# eu-gate.net
KiCad netlist of a schematic drawn in EAGLE
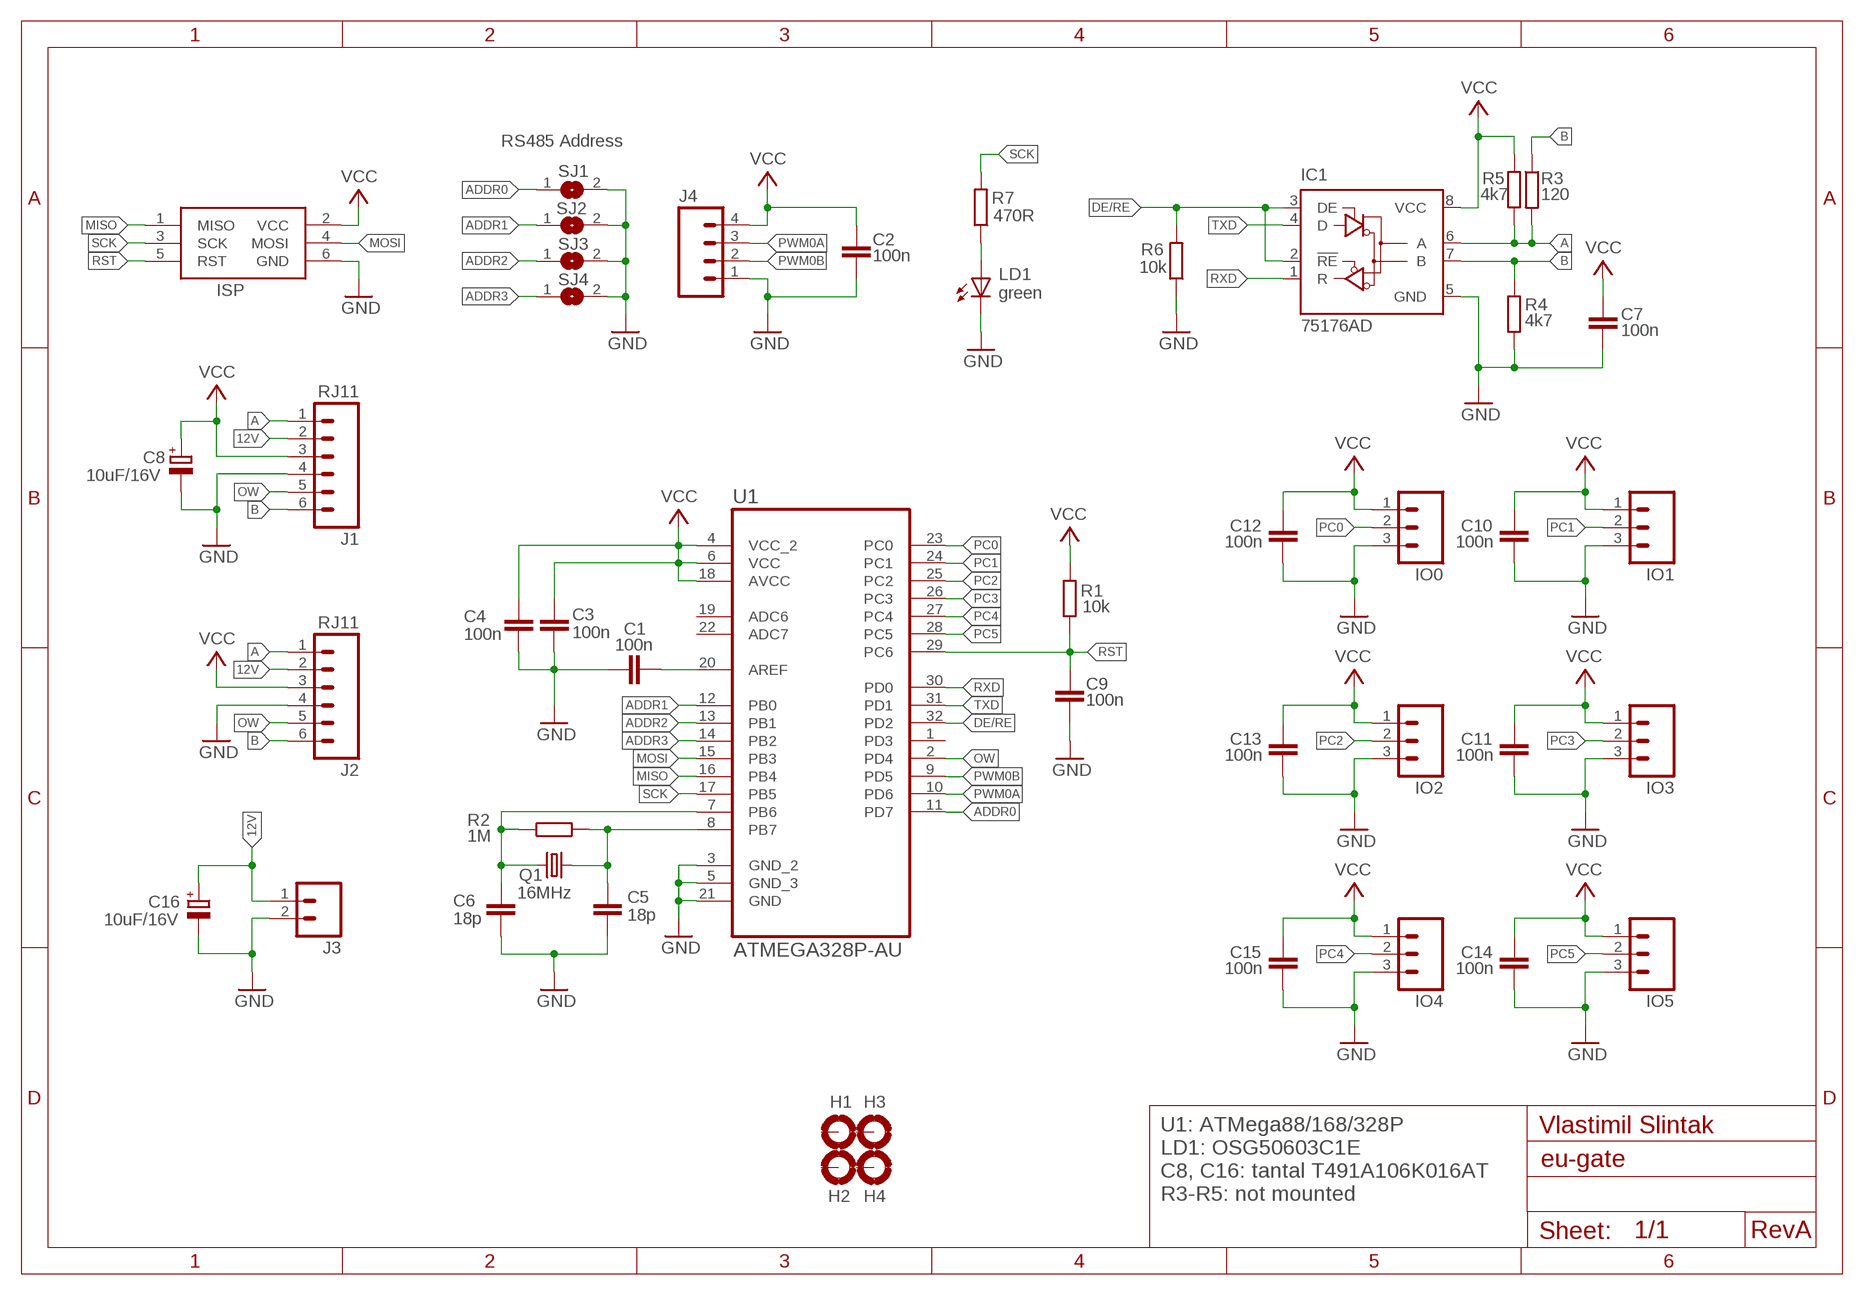
[diagram p0: schematic, sheet 1]

(export (version "E")
  (design (tool "Eeschema 10.0.6"))
  (components
    (comp (ref "C1")
      (value "100n")
      (footprint "eagle-import:C0603")
      (libsource (lib "eagle-import") (part "C-EUC0603"))
    )
    (comp (ref "C2")
      (value "100n")
      (footprint "eagle-import:C0603")
      (libsource (lib "eagle-import") (part "C-EUC0603"))
    )
    (comp (ref "C3")
      (value "100n")
      (footprint "eagle-import:C0603")
      (libsource (lib "eagle-import") (part "C-EUC0603"))
    )
    (comp (ref "C4")
      (value "100n")
      (footprint "eagle-import:C0603")
      (libsource (lib "eagle-import") (part "C-EUC0603"))
    )
    (comp (ref "C5")
      (value "18p")
      (footprint "eagle-import:C0603")
      (libsource (lib "eagle-import") (part "C-EUC0603"))
    )
    (comp (ref "C6")
      (value "18p")
      (footprint "eagle-import:C0603")
      (libsource (lib "eagle-import") (part "C-EUC0603"))
    )
    (comp (ref "C7")
      (value "100n")
      (footprint "eagle-import:C0603")
      (libsource (lib "eagle-import") (part "C-EUC0603"))
    )
    (comp (ref "C8")
      (value "10uF/16V")
      (footprint "eagle-import:SMC_A")
      (libsource (lib "eagle-import") (part "CPOL-EUSMCA"))
    )
    (comp (ref "C9")
      (value "100n")
      (footprint "eagle-import:C0603")
      (libsource (lib "eagle-import") (part "C-EUC0603"))
    )
    (comp (ref "C10")
      (value "100n")
      (footprint "eagle-import:C0603")
      (libsource (lib "eagle-import") (part "C-EUC0603"))
    )
    (comp (ref "C11")
      (value "100n")
      (footprint "eagle-import:C0603")
      (libsource (lib "eagle-import") (part "C-EUC0603"))
    )
    (comp (ref "C12")
      (value "100n")
      (footprint "eagle-import:C0603")
      (libsource (lib "eagle-import") (part "C-EUC0603"))
    )
    (comp (ref "C13")
      (value "100n")
      (footprint "eagle-import:C0603")
      (libsource (lib "eagle-import") (part "C-EUC0603"))
    )
    (comp (ref "C14")
      (value "100n")
      (footprint "eagle-import:C0603")
      (libsource (lib "eagle-import") (part "C-EUC0603"))
    )
    (comp (ref "C15")
      (value "100n")
      (footprint "eagle-import:C0603")
      (libsource (lib "eagle-import") (part "C-EUC0603"))
    )
    (comp (ref "C16")
      (value "10uF/16V")
      (footprint "eagle-import:SMC_A")
      (libsource (lib "eagle-import") (part "CPOL-EUSMCA"))
    )
    (comp (ref "H1")
      (value "MOUNT-PAD-ROUND3.0")
      (footprint "eagle-import:3,0-PAD")
      (libsource (lib "eagle-import") (part "MOUNT-PAD-ROUND3.0"))
    )
    (comp (ref "H2")
      (value "MOUNT-PAD-ROUND3.0")
      (footprint "eagle-import:3,0-PAD")
      (libsource (lib "eagle-import") (part "MOUNT-PAD-ROUND3.0"))
    )
    (comp (ref "H3")
      (value "MOUNT-PAD-ROUND3.0")
      (footprint "eagle-import:3,0-PAD")
      (libsource (lib "eagle-import") (part "MOUNT-PAD-ROUND3.0"))
    )
    (comp (ref "H4")
      (value "MOUNT-PAD-ROUND3.0")
      (footprint "eagle-import:3,0-PAD")
      (libsource (lib "eagle-import") (part "MOUNT-PAD-ROUND3.0"))
    )
    (comp (ref "IC1")
      (value "75176AD")
      (footprint "eagle-import:D_R-PDSO-G8")
      (libsource (lib "eagle-import") (part "75176AD"))
    )
    (comp (ref "IO0")
      (value "M03POLAR")
      (footprint "eagle-import:MOLEX-1X3")
      (libsource (lib "eagle-import") (part "M03POLAR"))
    )
    (comp (ref "IO1")
      (value "M03POLAR")
      (footprint "eagle-import:MOLEX-1X3")
      (libsource (lib "eagle-import") (part "M03POLAR"))
    )
    (comp (ref "IO2")
      (value "M03POLAR")
      (footprint "eagle-import:MOLEX-1X3")
      (libsource (lib "eagle-import") (part "M03POLAR"))
    )
    (comp (ref "IO3")
      (value "M03POLAR")
      (footprint "eagle-import:MOLEX-1X3")
      (libsource (lib "eagle-import") (part "M03POLAR"))
    )
    (comp (ref "IO4")
      (value "M03POLAR")
      (footprint "eagle-import:MOLEX-1X3")
      (libsource (lib "eagle-import") (part "M03POLAR"))
    )
    (comp (ref "IO5")
      (value "M03POLAR")
      (footprint "eagle-import:MOLEX-1X3")
      (libsource (lib "eagle-import") (part "M03POLAR"))
    )
    (comp (ref "ISP")
      (value "AVRISP-6")
      (footprint "eagle-import:AVRISP")
      (libsource (lib "eagle-import") (part "AVRISP-6"))
    )
    (comp (ref "J1")
      (value "RJ11")
      (footprint "eagle-import:RJ11-6")
      (libsource (lib "eagle-import") (part "RJ11-6PTH"))
    )
    (comp (ref "J2")
      (value "RJ11")
      (footprint "eagle-import:RJ11-6")
      (libsource (lib "eagle-import") (part "RJ11-6PTH"))
    )
    (comp (ref "J3")
      (value "M02POLAR")
      (footprint "eagle-import:MOLEX-1X2")
      (libsource (lib "eagle-import") (part "M02POLAR"))
    )
    (comp (ref "J4")
      (value "M04POLAR")
      (footprint "eagle-import:MOLEX-1X4")
      (libsource (lib "eagle-import") (part "M04POLAR"))
    )
    (comp (ref "LD1")
      (value "green")
      (footprint "eagle-import:CHIPLED_0603")
      (libsource (lib "eagle-import") (part "LEDCHIPLED_0603"))
    )
    (comp (ref "Q1")
      (value "16MHz")
      (footprint "eagle-import:HC49UP")
      (libsource (lib "eagle-import") (part "CRYSTALHC49UP"))
    )
    (comp (ref "R1")
      (value "10k")
      (footprint "eagle-import:R0603")
      (libsource (lib "eagle-import") (part "R-EU_R0603"))
    )
    (comp (ref "R2")
      (value "1M")
      (footprint "eagle-import:R0603")
      (libsource (lib "eagle-import") (part "R-EU_R0603"))
    )
    (comp (ref "R3")
      (value "120")
      (footprint "eagle-import:R0603")
      (libsource (lib "eagle-import") (part "R-EU_R0603"))
    )
    (comp (ref "R4")
      (value "4k7")
      (footprint "eagle-import:R0603")
      (libsource (lib "eagle-import") (part "R-EU_R0603"))
    )
    (comp (ref "R5")
      (value "4k7")
      (footprint "eagle-import:R0603")
      (libsource (lib "eagle-import") (part "R-EU_R0603"))
    )
    (comp (ref "R6")
      (value "10k")
      (footprint "eagle-import:R0603")
      (libsource (lib "eagle-import") (part "R-EU_R0603"))
    )
    (comp (ref "R7")
      (value "470R")
      (footprint "eagle-import:R0603")
      (libsource (lib "eagle-import") (part "R-EU_R0603"))
    )
    (comp (ref "SJ1") (value "SJ") (footprint "eagle-import:SJ") (libsource (lib "eagle-import") (part "SJ")))
    (comp (ref "SJ2") (value "SJ") (footprint "eagle-import:SJ") (libsource (lib "eagle-import") (part "SJ")))
    (comp (ref "SJ3") (value "SJ") (footprint "eagle-import:SJ") (libsource (lib "eagle-import") (part "SJ")))
    (comp (ref "SJ4") (value "SJ") (footprint "eagle-import:SJ") (libsource (lib "eagle-import") (part "SJ")))
    (comp (ref "U1")
      (value "ATMEGA328P-AU")
      (footprint "eagle-import:32TQFP")
      (libsource (lib "eagle-import") (part "ATMEGA328P-AU"))
    )
  )
  (nets
    (net (code "1") (name "12V") (class "Default")
      (node (ref "C16") (pin "+") (pinfunction "+_+") (pintype "passive"))
      (node (ref "J1") (pin "2") (pinfunction "2_2") (pintype "passive"))
      (node (ref "J2") (pin "2") (pinfunction "2_2") (pintype "passive"))
      (node (ref "J3") (pin "1") (pinfunction "1_1") (pintype "passive"))
    )
    (net (code "2") (name "A") (class "Default")
      (node (ref "IC1") (pin "6") (pinfunction "A_6") (pintype "output"))
      (node (ref "J1") (pin "1") (pinfunction "1_1") (pintype "passive"))
      (node (ref "J2") (pin "1") (pinfunction "1_1") (pintype "passive"))
      (node (ref "R3") (pin "2") (pinfunction "2_2") (pintype "passive"))
      (node (ref "R5") (pin "1") (pinfunction "1_1") (pintype "passive"))
    )
    (net (code "3") (name "ADDR0") (class "Default")
      (node (ref "SJ1") (pin "1") (pinfunction "1_1") (pintype "passive"))
      (node (ref "U1") (pin "11") (pinfunction "PD7_11") (pintype "bidirectional"))
    )
    (net (code "4") (name "ADDR1") (class "Default")
      (node (ref "SJ2") (pin "1") (pinfunction "1_1") (pintype "passive"))
      (node (ref "U1") (pin "12") (pinfunction "PB0_12") (pintype "bidirectional"))
    )
    (net (code "5") (name "ADDR2") (class "Default")
      (node (ref "SJ3") (pin "1") (pinfunction "1_1") (pintype "passive"))
      (node (ref "U1") (pin "13") (pinfunction "PB1_13") (pintype "bidirectional"))
    )
    (net (code "6") (name "ADDR3") (class "Default")
      (node (ref "SJ4") (pin "1") (pinfunction "1_1") (pintype "passive"))
      (node (ref "U1") (pin "14") (pinfunction "PB2_14") (pintype "bidirectional"))
    )
    (net (code "7") (name "B") (class "Default")
      (node (ref "IC1") (pin "7") (pinfunction "B_7") (pintype "output"))
      (node (ref "J1") (pin "6") (pinfunction "6_6") (pintype "passive"))
      (node (ref "J2") (pin "6") (pinfunction "6_6") (pintype "passive"))
      (node (ref "R3") (pin "1") (pinfunction "1_1") (pintype "passive"))
      (node (ref "R4") (pin "2") (pinfunction "2_2") (pintype "passive"))
    )
    (net (code "8") (name "DE{slash}RE") (class "Default")
      (node (ref "IC1") (pin "2") (pinfunction "~{RE}_2") (pintype "input"))
      (node (ref "IC1") (pin "3") (pinfunction "DE_3") (pintype "input"))
      (node (ref "R6") (pin "2") (pinfunction "2_2") (pintype "passive"))
      (node (ref "U1") (pin "32") (pinfunction "PD2_32") (pintype "bidirectional"))
    )
    (net (code "9") (name "GND") (class "Default")
      (node (ref "C1") (pin "1") (pinfunction "1_1") (pintype "passive"))
      (node (ref "C10") (pin "1") (pinfunction "1_1") (pintype "passive"))
      (node (ref "C11") (pin "1") (pinfunction "1_1") (pintype "passive"))
      (node (ref "C12") (pin "1") (pinfunction "1_1") (pintype "passive"))
      (node (ref "C13") (pin "1") (pinfunction "1_1") (pintype "passive"))
      (node (ref "C14") (pin "1") (pinfunction "1_1") (pintype "passive"))
      (node (ref "C15") (pin "1") (pinfunction "1_1") (pintype "passive"))
      (node (ref "C16") (pin "-") (pinfunction "-_-") (pintype "passive"))
      (node (ref "C2") (pin "1") (pinfunction "1_1") (pintype "passive"))
      (node (ref "C3") (pin "1") (pinfunction "1_1") (pintype "passive"))
      (node (ref "C4") (pin "1") (pinfunction "1_1") (pintype "passive"))
      (node (ref "C5") (pin "2") (pinfunction "2_2") (pintype "passive"))
      (node (ref "C6") (pin "2") (pinfunction "2_2") (pintype "passive"))
      (node (ref "C7") (pin "2") (pinfunction "2_2") (pintype "passive"))
      (node (ref "C8") (pin "-") (pinfunction "-_-") (pintype "passive"))
      (node (ref "C9") (pin "1") (pinfunction "1_1") (pintype "passive"))
      (node (ref "IC1") (pin "5") (pinfunction "GND_5") (pintype "power_in"))
      (node (ref "IO0") (pin "3") (pinfunction "3_3") (pintype "passive"))
      (node (ref "IO1") (pin "3") (pinfunction "3_3") (pintype "passive"))
      (node (ref "IO2") (pin "3") (pinfunction "3_3") (pintype "passive"))
      (node (ref "IO3") (pin "3") (pinfunction "3_3") (pintype "passive"))
      (node (ref "IO4") (pin "3") (pinfunction "3_3") (pintype "passive"))
      (node (ref "IO5") (pin "3") (pinfunction "3_3") (pintype "passive"))
      (node (ref "ISP") (pin "6") (pinfunction "GND_6") (pintype "power_in"))
      (node (ref "J1") (pin "4") (pinfunction "4_4") (pintype "passive"))
      (node (ref "J2") (pin "4") (pinfunction "4_4") (pintype "passive"))
      (node (ref "J3") (pin "2") (pinfunction "2_2") (pintype "passive"))
      (node (ref "J4") (pin "1") (pinfunction "1_1") (pintype "passive"))
      (node (ref "LD1") (pin "C") (pinfunction "C_C") (pintype "passive"))
      (node (ref "R4") (pin "1") (pinfunction "1_1") (pintype "passive"))
      (node (ref "R6") (pin "1") (pinfunction "1_1") (pintype "passive"))
      (node (ref "SJ1") (pin "2") (pinfunction "2_2") (pintype "passive"))
      (node (ref "SJ2") (pin "2") (pinfunction "2_2") (pintype "passive"))
      (node (ref "SJ3") (pin "2") (pinfunction "2_2") (pintype "passive"))
      (node (ref "SJ4") (pin "2") (pinfunction "2_2") (pintype "passive"))
      (node (ref "U1") (pin "21") (pinfunction "GND_21") (pintype "passive"))
      (node (ref "U1") (pin "3") (pinfunction "GND_2_3") (pintype "passive"))
      (node (ref "U1") (pin "5") (pinfunction "GND_3_5") (pintype "passive"))
    )
    (net (code "10") (name "MISO") (class "Default")
      (node (ref "ISP") (pin "1") (pinfunction "MISO_1") (pintype "input"))
      (node (ref "U1") (pin "16") (pinfunction "PB4_16") (pintype "bidirectional"))
    )
    (net (code "11") (name "MOSI") (class "Default")
      (node (ref "ISP") (pin "4") (pinfunction "MOSI_4") (pintype "output"))
      (node (ref "U1") (pin "15") (pinfunction "PB3_15") (pintype "bidirectional"))
    )
    (net (code "12") (name "Net-(LD1-PadA)") (class "Default")
      (node (ref "LD1") (pin "A") (pinfunction "A_A") (pintype "passive"))
      (node (ref "R7") (pin "1") (pinfunction "1_1") (pintype "passive"))
    )
    (net (code "13") (name "Net-(U1-AREF)") (class "Default")
      (node (ref "C1") (pin "2") (pinfunction "2_2") (pintype "passive"))
      (node (ref "U1") (pin "20") (pinfunction "AREF_20") (pintype "input"))
    )
    (net (code "14") (name "Net-(U1-PB6)") (class "Default")
      (node (ref "C6") (pin "1") (pinfunction "1_1") (pintype "passive"))
      (node (ref "Q1") (pin "2") (pinfunction "2_2") (pintype "passive"))
      (node (ref "R2") (pin "1") (pinfunction "1_1") (pintype "passive"))
      (node (ref "U1") (pin "7") (pinfunction "PB6_7") (pintype "bidirectional"))
    )
    (net (code "15") (name "Net-(U1-PB7)") (class "Default")
      (node (ref "C5") (pin "1") (pinfunction "1_1") (pintype "passive"))
      (node (ref "Q1") (pin "1") (pinfunction "1_1") (pintype "passive"))
      (node (ref "R2") (pin "2") (pinfunction "2_2") (pintype "passive"))
      (node (ref "U1") (pin "8") (pinfunction "PB7_8") (pintype "bidirectional"))
    )
    (net (code "16") (name "OW") (class "Default")
      (node (ref "J1") (pin "5") (pinfunction "5_5") (pintype "passive"))
      (node (ref "J2") (pin "5") (pinfunction "5_5") (pintype "passive"))
      (node (ref "U1") (pin "2") (pinfunction "PD4_2") (pintype "bidirectional"))
    )
    (net (code "17") (name "PC0") (class "Default")
      (node (ref "IO0") (pin "2") (pinfunction "2_2") (pintype "passive"))
      (node (ref "U1") (pin "23") (pinfunction "PC0_23") (pintype "bidirectional"))
    )
    (net (code "18") (name "PC1") (class "Default")
      (node (ref "IO1") (pin "2") (pinfunction "2_2") (pintype "passive"))
      (node (ref "U1") (pin "24") (pinfunction "PC1_24") (pintype "bidirectional"))
    )
    (net (code "19") (name "PC2") (class "Default")
      (node (ref "IO2") (pin "2") (pinfunction "2_2") (pintype "passive"))
      (node (ref "U1") (pin "25") (pinfunction "PC2_25") (pintype "bidirectional"))
    )
    (net (code "20") (name "PC3") (class "Default")
      (node (ref "IO3") (pin "2") (pinfunction "2_2") (pintype "passive"))
      (node (ref "U1") (pin "26") (pinfunction "PC3_26") (pintype "bidirectional"))
    )
    (net (code "21") (name "PC4") (class "Default")
      (node (ref "IO4") (pin "2") (pinfunction "2_2") (pintype "passive"))
      (node (ref "U1") (pin "27") (pinfunction "PC4_27") (pintype "bidirectional"))
    )
    (net (code "22") (name "PC5") (class "Default")
      (node (ref "IO5") (pin "2") (pinfunction "2_2") (pintype "passive"))
      (node (ref "U1") (pin "28") (pinfunction "PC5_28") (pintype "bidirectional"))
    )
    (net (code "23") (name "PWM0A") (class "Default")
      (node (ref "J4") (pin "3") (pinfunction "3_3") (pintype "passive"))
      (node (ref "U1") (pin "10") (pinfunction "PD6_10") (pintype "bidirectional"))
    )
    (net (code "24") (name "PWM0B") (class "Default")
      (node (ref "J4") (pin "2") (pinfunction "2_2") (pintype "passive"))
      (node (ref "U1") (pin "9") (pinfunction "PD5_9") (pintype "bidirectional"))
    )
    (net (code "25") (name "RST") (class "Default")
      (node (ref "C9") (pin "2") (pinfunction "2_2") (pintype "passive"))
      (node (ref "ISP") (pin "5") (pinfunction "RST_5") (pintype "output"))
      (node (ref "R1") (pin "1") (pinfunction "1_1") (pintype "passive"))
      (node (ref "U1") (pin "29") (pinfunction "PC6_29") (pintype "bidirectional"))
    )
    (net (code "26") (name "RXD") (class "Default")
      (node (ref "IC1") (pin "1") (pinfunction "R_1") (pintype "input"))
      (node (ref "U1") (pin "30") (pinfunction "PD0_30") (pintype "bidirectional"))
    )
    (net (code "27") (name "SCK") (class "Default")
      (node (ref "ISP") (pin "3") (pinfunction "SCK_3") (pintype "output"))
      (node (ref "R7") (pin "2") (pinfunction "2_2") (pintype "passive"))
      (node (ref "U1") (pin "17") (pinfunction "PB5_17") (pintype "bidirectional"))
    )
    (net (code "28") (name "TXD") (class "Default")
      (node (ref "IC1") (pin "4") (pinfunction "D_4") (pintype "input"))
      (node (ref "U1") (pin "31") (pinfunction "PD1_31") (pintype "bidirectional"))
    )
    (net (code "29") (name "VCC") (class "Default")
      (node (ref "C10") (pin "2") (pinfunction "2_2") (pintype "passive"))
      (node (ref "C11") (pin "2") (pinfunction "2_2") (pintype "passive"))
      (node (ref "C12") (pin "2") (pinfunction "2_2") (pintype "passive"))
      (node (ref "C13") (pin "2") (pinfunction "2_2") (pintype "passive"))
      (node (ref "C14") (pin "2") (pinfunction "2_2") (pintype "passive"))
      (node (ref "C15") (pin "2") (pinfunction "2_2") (pintype "passive"))
      (node (ref "C2") (pin "2") (pinfunction "2_2") (pintype "passive"))
      (node (ref "C3") (pin "2") (pinfunction "2_2") (pintype "passive"))
      (node (ref "C4") (pin "2") (pinfunction "2_2") (pintype "passive"))
      (node (ref "C7") (pin "1") (pinfunction "1_1") (pintype "passive"))
      (node (ref "C8") (pin "+") (pinfunction "+_+") (pintype "passive"))
      (node (ref "IC1") (pin "8") (pinfunction "VCC_8") (pintype "power_in"))
      (node (ref "IO0") (pin "1") (pinfunction "1_1") (pintype "passive"))
      (node (ref "IO1") (pin "1") (pinfunction "1_1") (pintype "passive"))
      (node (ref "IO2") (pin "1") (pinfunction "1_1") (pintype "passive"))
      (node (ref "IO3") (pin "1") (pinfunction "1_1") (pintype "passive"))
      (node (ref "IO4") (pin "1") (pinfunction "1_1") (pintype "passive"))
      (node (ref "IO5") (pin "1") (pinfunction "1_1") (pintype "passive"))
      (node (ref "ISP") (pin "2") (pinfunction "VCC_2") (pintype "power_in"))
      (node (ref "J1") (pin "3") (pinfunction "3_3") (pintype "passive"))
      (node (ref "J2") (pin "3") (pinfunction "3_3") (pintype "passive"))
      (node (ref "J4") (pin "4") (pinfunction "4_4") (pintype "passive"))
      (node (ref "R1") (pin "2") (pinfunction "2_2") (pintype "passive"))
      (node (ref "R5") (pin "2") (pinfunction "2_2") (pintype "passive"))
      (node (ref "U1") (pin "18") (pinfunction "AVCC_18") (pintype "power_in"))
      (node (ref "U1") (pin "4") (pinfunction "VCC_2_4") (pintype "power_in"))
      (node (ref "U1") (pin "6") (pinfunction "VCC_6") (pintype "power_in"))
    )
    (net (code "30") (name "unconnected-(H1-MOUNT-PadB3,0)") (class "Default")
      (node (ref "H1") (pin "B3,0") (pinfunction "MOUNT_B3,0") (pintype "passive"))
    )
    (net (code "31") (name "unconnected-(H2-MOUNT-PadB3,0)") (class "Default")
      (node (ref "H2") (pin "B3,0") (pinfunction "MOUNT_B3,0") (pintype "passive"))
    )
    (net (code "32") (name "unconnected-(H3-MOUNT-PadB3,0)") (class "Default")
      (node (ref "H3") (pin "B3,0") (pinfunction "MOUNT_B3,0") (pintype "passive"))
    )
    (net (code "33") (name "unconnected-(H4-MOUNT-PadB3,0)") (class "Default")
      (node (ref "H4") (pin "B3,0") (pinfunction "MOUNT_B3,0") (pintype "passive"))
    )
    (net (code "34") (name "unconnected-(U1-ADC6-Pad19)") (class "Default")
      (node (ref "U1") (pin "19") (pinfunction "ADC6_19") (pintype "input"))
    )
    (net (code "35") (name "unconnected-(U1-ADC7-Pad22)") (class "Default")
      (node (ref "U1") (pin "22") (pinfunction "ADC7_22") (pintype "input"))
    )
    (net (code "36") (name "unconnected-(U1-PD3-Pad1)") (class "Default")
      (node (ref "U1") (pin "1") (pinfunction "PD3_1") (pintype "bidirectional"))
    )
  )
)
